# Super-Regenerative-FM-Tuner-ForcedQuench.net
KiCad netlist of a schematic drawn in EAGLE
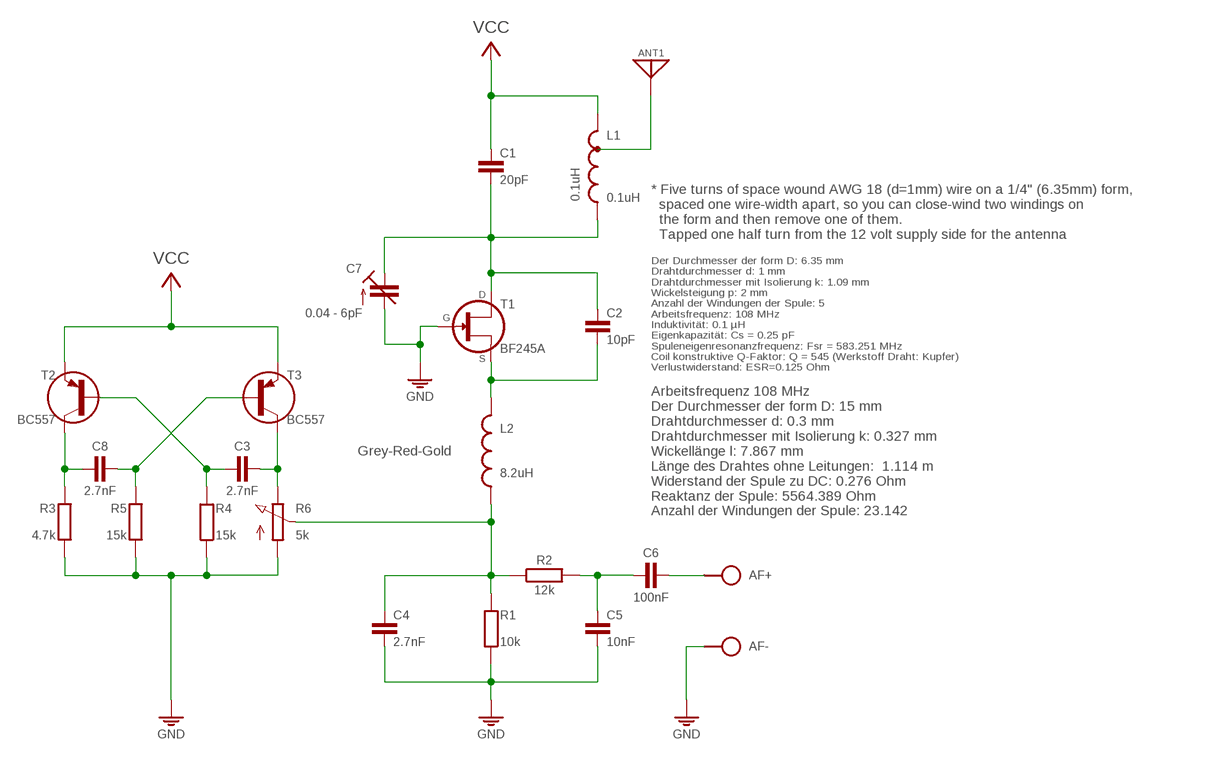
[diagram p0: schematic, sheet 1]

(export (version "E")
  (design (tool "Eeschema 10.0.6"))
  (components
    (comp (ref "AF")
      (value "SPAD+-+-")
      (footprint "eagle-import:SPAD+-")
      (libsource (lib "eagle-import") (part "SPAD+-+-"))
    )
    (comp (ref "ANT1")
      (value "ANT")
      (footprint "eagle-import:SPAD")
      (libsource (lib "eagle-import") (part "ANT"))
    )
    (comp (ref "C1")
      (value "20pF")
      (footprint "eagle-import:C025-015X024")
      (libsource (lib "eagle-import") (part "C025-015X024"))
    )
    (comp (ref "C2")
      (value "10pF")
      (footprint "eagle-import:C025-015X024")
      (libsource (lib "eagle-import") (part "C025-015X024"))
    )
    (comp (ref "C3")
      (value "2.7nF")
      (footprint "eagle-import:C0750-020X044")
      (libsource (lib "eagle-import") (part "C-H075-020X044"))
    )
    (comp (ref "C4")
      (value "2.7nF")
      (footprint "eagle-import:C050-020X044@1")
      (libsource (lib "eagle-import") (part "C050-020X044"))
    )
    (comp (ref "C5")
      (value "10nF")
      (footprint "eagle-import:C050-020X044@1")
      (libsource (lib "eagle-import") (part "C050-020X044"))
    )
    (comp (ref "C6")
      (value "100nF")
      (footprint "eagle-import:C050-020X044")
      (libsource (lib "eagle-import") (part "C-H050-020X044"))
    )
    (comp (ref "C7")
      (value "0.04 - 6pF")
      (footprint "eagle-import:CTRIMTZ03")
      (libsource (lib "eagle-import") (part "C-TR-PH20127-TZ03"))
    )
    (comp (ref "C8")
      (value "2.7nF")
      (footprint "eagle-import:C0750-020X044")
      (libsource (lib "eagle-import") (part "C-H075-020X044"))
    )
    (comp (ref "L1")
      (value "0.1uH")
      (footprint "eagle-import:L-08_10-TAP1")
      (libsource (lib "eagle-import") (part "L-TAP1L-08/10-TAP1"))
    )
    (comp (ref "L2")
      (value "8.2uH")
      (footprint "eagle-import:L-04_7-V")
      (libsource (lib "eagle-import") (part "L04/7-V"))
    )
    (comp (ref "PWR")
      (value "VCC_GNDL")
      (footprint "eagle-import:SPAD-+")
      (libsource (lib "eagle-import") (part "VCC_GNDL"))
    )
    (comp (ref "R1")
      (value "10k")
      (footprint "eagle-import:0204_7")
      (libsource (lib "eagle-import") (part "R0204/7"))
    )
    (comp (ref "R2")
      (value "12k")
      (footprint "eagle-import:0204_7")
      (libsource (lib "eagle-import") (part "R-H0204/7"))
    )
    (comp (ref "R3")
      (value "4.7k")
      (footprint "eagle-import:0202_7-V")
      (libsource (lib "eagle-import") (part "R0202/7-V"))
    )
    (comp (ref "R4")
      (value "15k")
      (footprint "eagle-import:0202_7-V")
      (libsource (lib "eagle-import") (part "R0202/7-V"))
    )
    (comp (ref "R5")
      (value "15k")
      (footprint "eagle-import:0202_7-V")
      (libsource (lib "eagle-import") (part "R0202/7-V"))
    )
    (comp (ref "R6")
      (value "5k")
      (footprint "eagle-import:POT-V")
      (libsource (lib "eagle-import") (part "POT-V"))
    )
    (comp (ref "T1")
      (value "BF245A")
      (footprint "eagle-import:TO92-GSD")
      (libsource (lib "eagle-import") (part "BF245BTO92"))
    )
    (comp (ref "T2")
      (value "BC557")
      (footprint "eagle-import:TO92-CBE")
      (libsource (lib "eagle-import") (part "BC557CBE"))
    )
    (comp (ref "T3")
      (value "BC557")
      (footprint "eagle-import:TO92-CBE")
      (libsource (lib "eagle-import") (part "BC557CBE"))
    )
  )
  (nets
    (net (code "1") (name "GND") (class "Default")
      (node (ref "AF") (pin "1") (pinfunction "P$1_1") (pintype "passive"))
      (node (ref "C4") (pin "2") (pinfunction "2_2") (pintype "passive"))
      (node (ref "C5") (pin "2") (pinfunction "2_2") (pintype "passive"))
      (node (ref "C7") (pin "1") (pinfunction "A_1") (pintype "passive"))
      (node (ref "PWR") (pin "1") (pinfunction "GND_1") (pintype "power_in"))
      (node (ref "R1") (pin "1") (pinfunction "2_1") (pintype "passive"))
      (node (ref "R3") (pin "1") (pinfunction "2_1") (pintype "passive"))
      (node (ref "R4") (pin "1") (pinfunction "2_1") (pintype "passive"))
      (node (ref "R5") (pin "1") (pinfunction "2_1") (pintype "passive"))
      (node (ref "R6") (pin "A") (pinfunction "A_A") (pintype "passive"))
      (node (ref "T1") (pin "1") (pinfunction "G_1") (pintype "passive"))
    )
    (net (code "2") (name "Net-(AFA-P$1)") (class "Default")
      (node (ref "AF") (pin "2") (pinfunction "P$1_2") (pintype "passive"))
      (node (ref "C6") (pin "2") (pinfunction "2_2") (pintype "passive"))
    )
    (net (code "3") (name "Net-(C3-Pad2)") (class "Default")
      (node (ref "C3") (pin "2") (pinfunction "2_2") (pintype "passive"))
      (node (ref "R6") (pin "E") (pinfunction "E_E") (pintype "passive"))
      (node (ref "T3") (pin "C") (pinfunction "C_C") (pintype "passive"))
    )
    (net (code "4") (name "Net-(C5-Pad1)") (class "Default")
      (node (ref "C5") (pin "1") (pinfunction "1_1") (pintype "passive"))
      (node (ref "C6") (pin "1") (pinfunction "1_1") (pintype "passive"))
      (node (ref "R2") (pin "2") (pinfunction "2_2") (pintype "passive"))
    )
    (net (code "5") (name "Net-(C7-E)") (class "Default")
      (node (ref "C1") (pin "2") (pinfunction "2_2") (pintype "passive"))
      (node (ref "C2") (pin "1") (pinfunction "1_1") (pintype "passive"))
      (node (ref "C7") (pin "2") (pinfunction "E_2") (pintype "passive"))
      (node (ref "L1") (pin "2") (pinfunction "2_2") (pintype "passive"))
      (node (ref "T1") (pin "3") (pinfunction "D_3") (pintype "passive"))
    )
    (net (code "6") (name "Net-(L1-T)") (class "Default")
      (node (ref "ANT1") (pin "1") (pinfunction "1_1") (pintype "output"))
      (node (ref "L1") (pin "3") (pinfunction "T_3") (pintype "passive"))
    )
    (net (code "7") (name "Net-(R1-1)") (class "Default")
      (node (ref "C4") (pin "1") (pinfunction "1_1") (pintype "passive"))
      (node (ref "L2") (pin "2") (pinfunction "2_2") (pintype "passive"))
      (node (ref "R1") (pin "2") (pinfunction "1_2") (pintype "passive"))
      (node (ref "R2") (pin "1") (pinfunction "1_1") (pintype "passive"))
      (node (ref "R6") (pin "S") (pinfunction "S_S") (pintype "passive"))
    )
    (net (code "8") (name "Net-(R3-1)") (class "Default")
      (node (ref "C8") (pin "1") (pinfunction "1_1") (pintype "passive"))
      (node (ref "R3") (pin "2") (pinfunction "1_2") (pintype "passive"))
      (node (ref "T2") (pin "C") (pinfunction "C_C") (pintype "passive"))
    )
    (net (code "9") (name "Net-(R4-1)") (class "Default")
      (node (ref "C3") (pin "1") (pinfunction "1_1") (pintype "passive"))
      (node (ref "R4") (pin "2") (pinfunction "1_2") (pintype "passive"))
      (node (ref "T2") (pin "B") (pinfunction "B_B") (pintype "passive"))
    )
    (net (code "10") (name "Net-(R5-1)") (class "Default")
      (node (ref "C8") (pin "2") (pinfunction "2_2") (pintype "passive"))
      (node (ref "R5") (pin "2") (pinfunction "1_2") (pintype "passive"))
      (node (ref "T3") (pin "B") (pinfunction "B_B") (pintype "passive"))
    )
    (net (code "11") (name "Net-(T1-S)") (class "Default")
      (node (ref "C2") (pin "2") (pinfunction "2_2") (pintype "passive"))
      (node (ref "L2") (pin "1") (pinfunction "1_1") (pintype "passive"))
      (node (ref "T1") (pin "2") (pinfunction "S_2") (pintype "passive"))
    )
    (net (code "12") (name "VCC") (class "Default")
      (node (ref "C1") (pin "1") (pinfunction "1_1") (pintype "passive"))
      (node (ref "L1") (pin "1") (pinfunction "1_1") (pintype "passive"))
      (node (ref "PWR") (pin "2") (pinfunction "VCC_2") (pintype "power_in"))
      (node (ref "T2") (pin "E") (pinfunction "E_E") (pintype "passive"))
      (node (ref "T3") (pin "E") (pinfunction "E_E") (pintype "passive"))
    )
  )
)
